# ChargeLevel.net
KiCad netlist of a schematic drawn in Altium Designer
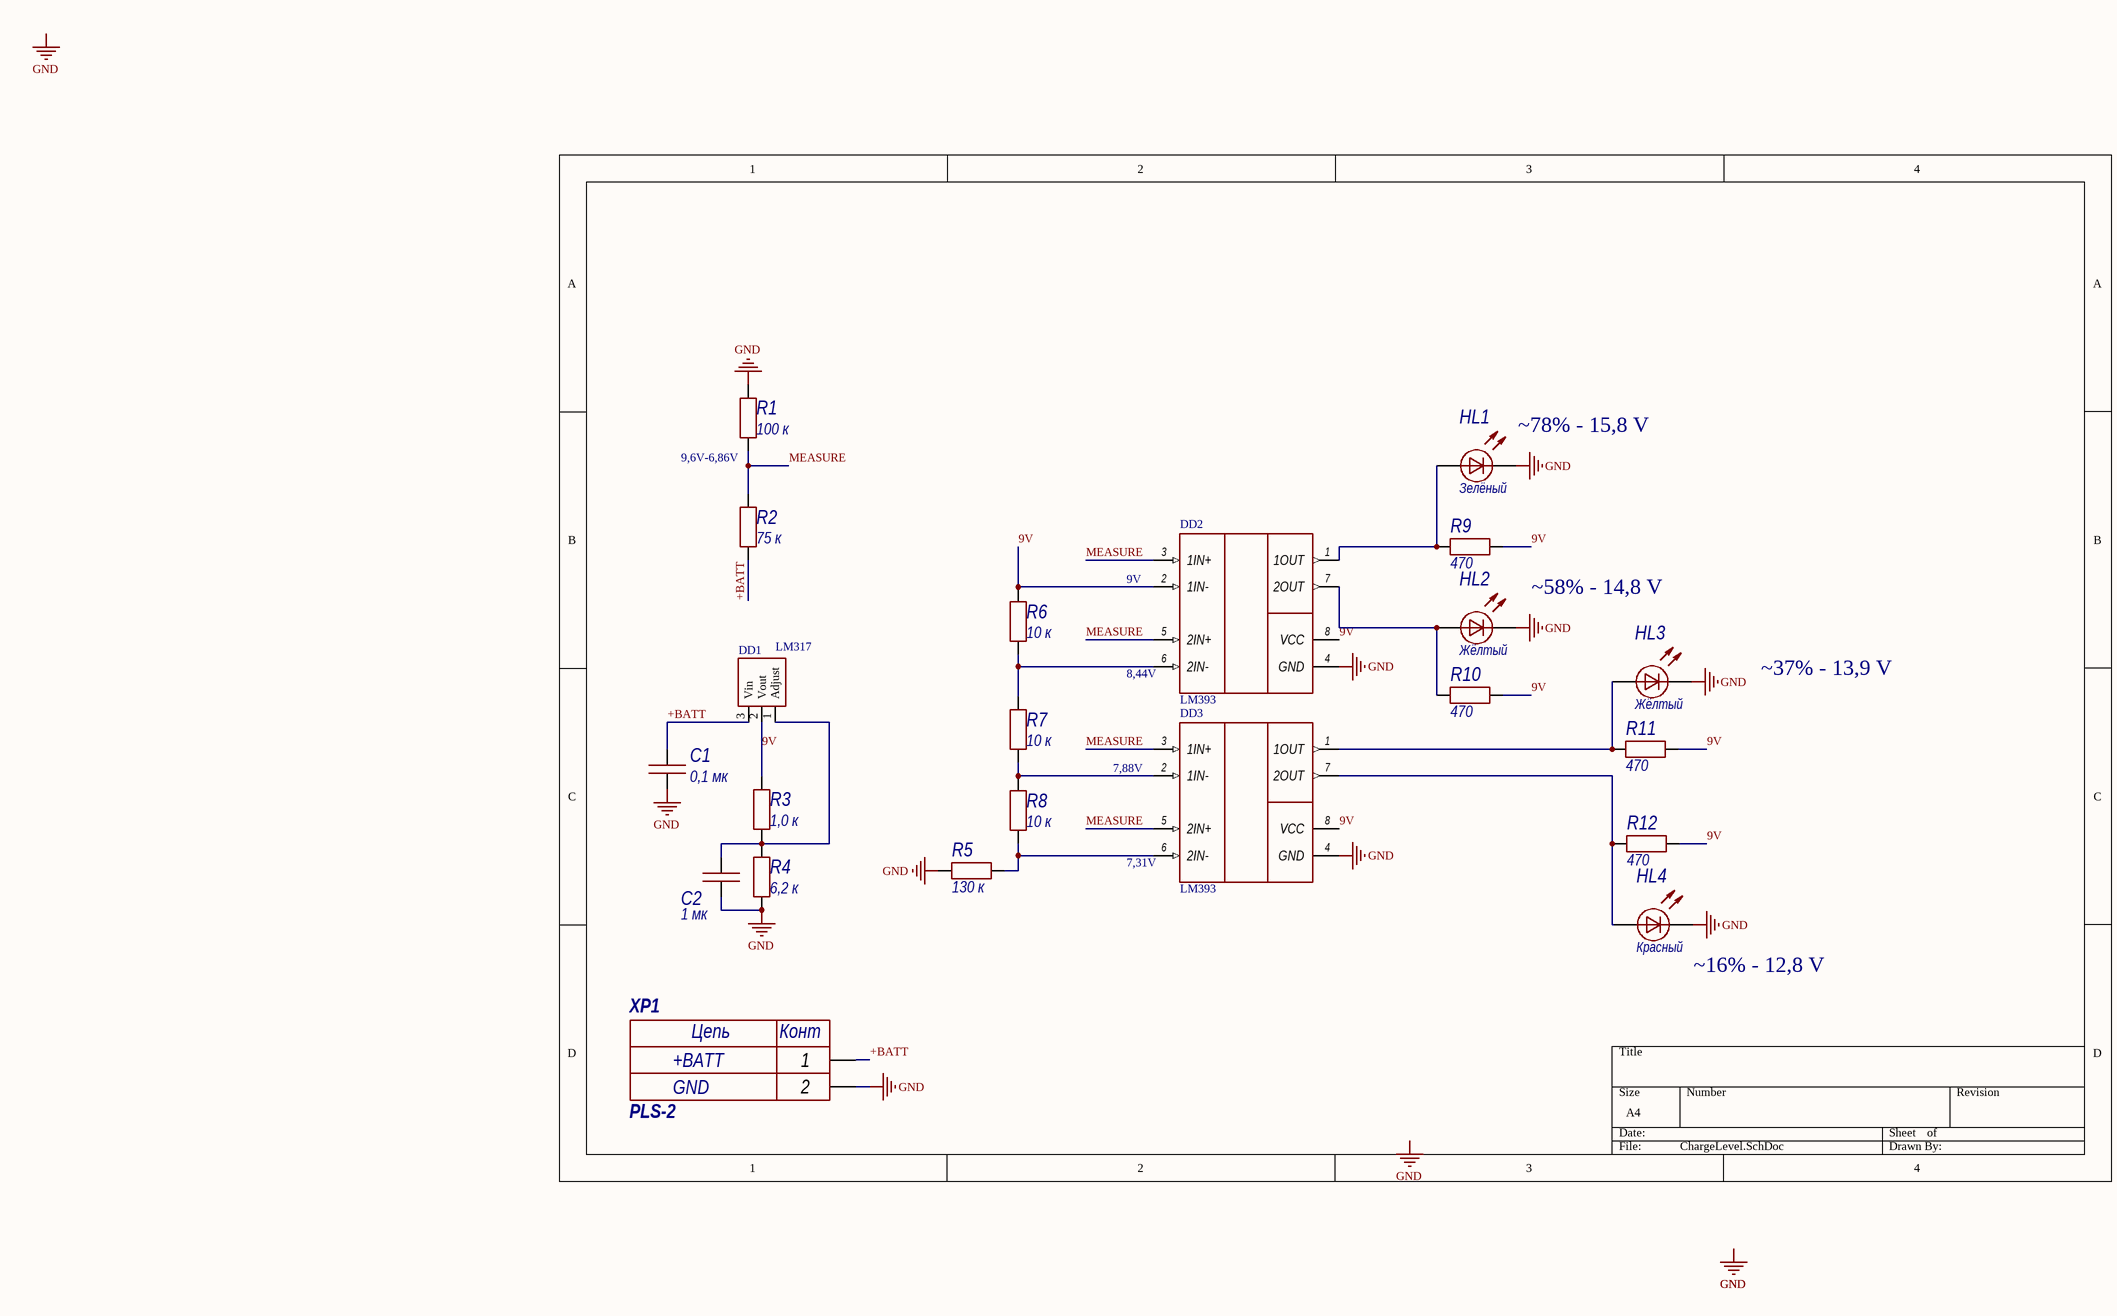
[diagram p0: ChargeLevel.SchDoc]

(export (version "E")
  (design (tool "Eeschema 10.0.6"))
  (components
    (comp (ref "C1")
      (value "0,1 мк")
      (footprint "0603C")
      (description "Конденсатор")
      (fields (field (name "PART NUMBER") "Capacitor"))
      (libsource (lib "Hydrolib") (part "Capacitor"))
    )
    (comp (ref "C2")
      (value "1 мк")
      (footprint "0603C")
      (description "Конденсатор")
      (fields (field (name "PART NUMBER") "Capacitor"))
      (libsource (lib "Hydrolib") (part "Capacitor"))
    )
    (comp (ref "DD1") (value "LM317") (footprint "TO-220") (libsource (lib "LM317") (part "LM317")))
    (comp (ref "DD2")
      (value "LM393")
      (footprint "SOIC-8")
      (description "Двойной маломощный компаратор напряжения")
      (fields
        (field (name "MF") "Texas Instruments")
        (field (name "MP") "LM393D")
        (field (name "АВТОР") "rreali")
      )
      (libsource (lib "Hydrolib") (part "LM393"))
    )
    (comp (ref "DD3")
      (value "LM393")
      (footprint "SOIC-8")
      (description "Двойной маломощный компаратор напряжения")
      (fields
        (field (name "MF") "Texas Instruments")
        (field (name "MP") "LM393D")
        (field (name "АВТОР") "rreali")
      )
      (libsource (lib "Hydrolib") (part "LM393"))
    )
    (comp (ref "HL1")
      (value "Зелёный")
      (footprint "0603D_green")
      (description "Светодиод 0603 Зелёный")
      (fields (field (name "PART NUMBER") "LED 0603 GREEN") (field (name "АВТОР") "rreali"))
      (libsource (lib "Hydrolib") (part "LED"))
    )
    (comp (ref "HL2")
      (value "Жёлтый")
      (footprint "0603D_yellow")
      (description "Светодиод 0603 Жёлтый")
      (fields (field (name "PART NUMBER") "LED 0603 YELLOW") (field (name "АВТОР") "rreali"))
      (libsource (lib "Hydrolib") (part "LED"))
    )
    (comp (ref "HL3")
      (value "Жёлтый")
      (footprint "0603D_yellow")
      (description "Светодиод 0603 Жёлтый")
      (fields (field (name "PART NUMBER") "LED 0603 YELLOW") (field (name "АВТОР") "rreali"))
      (libsource (lib "Hydrolib") (part "LED"))
    )
    (comp (ref "HL4")
      (value "Красный")
      (footprint "0603D_red")
      (description "Светодиод 0603 Красный")
      (fields (field (name "PART NUMBER") "LED 0603 RED") (field (name "АВТОР") "rreali"))
      (libsource (lib "Hydrolib") (part "LED"))
    )
    (comp (ref "R1")
      (value "100 к")
      (footprint "0603R")
      (description "Резистор номиналом 100 кОм 1%")
      (fields (field (name "PART NUMBER") "Resistor_100k_1_0603") (field (name "TOLERANCE") "1%"))
      (libsource (lib "") (part "Resistor_1"))
    )
    (comp (ref "R2")
      (value "75 к")
      (footprint "0603R")
      (description "Резистор номиналом 75 кОм 1%")
      (fields (field (name "PART NUMBER") "Resistor_75k_1_0603") (field (name "TOLERANCE") "1%"))
      (libsource (lib "") (part "Resistor_1"))
    )
    (comp (ref "R3")
      (value "1,0 к")
      (footprint "0603R")
      (description "Резистор номиналом 1,0 кОм 1%")
      (fields (field (name "PART NUMBER") "Resistor_1.0k_1_0603") (field (name "TOLERANCE") "1%"))
      (libsource (lib "") (part "Resistor_1"))
    )
    (comp (ref "R4")
      (value "6,2 к")
      (footprint "0603R")
      (description "Резистор номиналом 6,2 кОм 1%")
      (fields (field (name "PART NUMBER") "Resistor_6.2k_1_0603") (field (name "TOLERANCE") "1%"))
      (libsource (lib "") (part "Resistor_1"))
    )
    (comp (ref "R5")
      (value "130 к")
      (footprint "0603R")
      (description "Резистор номиналом 130 кОм 1%")
      (fields (field (name "PART NUMBER") "Resistor_130k_1_0603") (field (name "TOLERANCE") "1%"))
      (libsource (lib "Hydrolib") (part "Resistor"))
    )
    (comp (ref "R6")
      (value "10 к")
      (footprint "0603R")
      (description "Резистор номиналом 10 кОм 1%")
      (fields (field (name "PART NUMBER") "Resistor_10k_1_0603") (field (name "TOLERANCE") "1%"))
      (libsource (lib "") (part "Resistor_1"))
    )
    (comp (ref "R7")
      (value "10 к")
      (footprint "0603R")
      (description "Резистор номиналом 10 кОм 1%")
      (fields (field (name "PART NUMBER") "Resistor_10k_1_0603") (field (name "TOLERANCE") "1%"))
      (libsource (lib "") (part "Resistor_1"))
    )
    (comp (ref "R8")
      (value "10 к")
      (footprint "0603R")
      (description "Резистор номиналом 10 кОм 1%")
      (fields (field (name "PART NUMBER") "Resistor_10k_1_0603") (field (name "TOLERANCE") "1%"))
      (libsource (lib "") (part "Resistor_1"))
    )
    (comp (ref "R9")
      (value "470")
      (footprint "0603R")
      (description "Резистор номиналом 470 Ом 1%")
      (fields (field (name "PART NUMBER") "Resistor_470_1_0603") (field (name "TOLERANCE") "1%"))
      (libsource (lib "Hydrolib") (part "Resistor"))
    )
    (comp (ref "R10")
      (value "470")
      (footprint "0603R")
      (description "Резистор номиналом 470 Ом 1%")
      (fields (field (name "PART NUMBER") "Resistor_470_1_0603") (field (name "TOLERANCE") "1%"))
      (libsource (lib "Hydrolib") (part "Resistor"))
    )
    (comp (ref "R11")
      (value "470")
      (footprint "0603R")
      (description "Резистор номиналом 470 Ом 1%")
      (fields (field (name "PART NUMBER") "Resistor_470_1_0603") (field (name "TOLERANCE") "1%"))
      (libsource (lib "Hydrolib") (part "Resistor"))
    )
    (comp (ref "R12")
      (value "470")
      (footprint "0603R")
      (description "Резистор номиналом 470 Ом 1%")
      (fields (field (name "PART NUMBER") "Resistor_470_1_0603") (field (name "TOLERANCE") "1%"))
      (libsource (lib "Hydrolib") (part "Resistor"))
    )
    (comp (ref "XP1")
      (value "PLS-2")
      (footprint "PLS2")
      (description "Гребенка 2 пина")
      (fields (field (name "VALUE2") "GND") (field (name "VALUE1") "+BATT") (field (name "АВТОР") "rreali"))
      (libsource (lib "Hydrolib") (part "Conn_2pin"))
    )
  )
  (nets
    (net (code "1") (name "/+BATT") (class "Default")
      (node (ref "C1") (pin "1") (pinfunction "1_1") (pintype "passive"))
      (node (ref "DD1") (pin "3") (pinfunction "Vin_3") (pintype "passive"))
      (node (ref "R2") (pin "1") (pinfunction "1_1") (pintype "passive"))
      (node (ref "XP1") (pin "1") (pinfunction "1_1") (pintype "passive"))
    )
    (net (code "2") (name "/9V") (class "Default")
      (node (ref "DD1") (pin "2") (pinfunction "Vout_2") (pintype "passive"))
      (node (ref "DD2") (pin "2") (pinfunction "1IN-_2") (pintype "input"))
      (node (ref "DD2") (pin "8") (pinfunction "VCC_8") (pintype "power_in"))
      (node (ref "DD3") (pin "8") (pinfunction "VCC_8") (pintype "power_in"))
      (node (ref "R10") (pin "2") (pinfunction "2_2") (pintype "passive"))
      (node (ref "R11") (pin "2") (pinfunction "2_2") (pintype "passive"))
      (node (ref "R12") (pin "2") (pinfunction "2_2") (pintype "passive"))
      (node (ref "R3") (pin "2") (pinfunction "2_2") (pintype "passive"))
      (node (ref "R6") (pin "2") (pinfunction "2_2") (pintype "passive"))
      (node (ref "R9") (pin "2") (pinfunction "2_2") (pintype "passive"))
    )
    (net (code "3") (name "/MEASURE") (class "Default")
      (node (ref "DD2") (pin "3") (pinfunction "1IN+_3") (pintype "input"))
      (node (ref "DD2") (pin "5") (pinfunction "2IN+_5") (pintype "input"))
      (node (ref "DD3") (pin "3") (pinfunction "1IN+_3") (pintype "input"))
      (node (ref "DD3") (pin "5") (pinfunction "2IN+_5") (pintype "input"))
      (node (ref "R1") (pin "1") (pinfunction "1_1") (pintype "passive"))
      (node (ref "R2") (pin "2") (pinfunction "2_2") (pintype "passive"))
    )
    (net (code "4") (name "GND") (class "Default")
      (node (ref "C1") (pin "2") (pinfunction "2_2") (pintype "passive"))
      (node (ref "C2") (pin "2") (pinfunction "2_2") (pintype "passive"))
      (node (ref "DD2") (pin "4") (pinfunction "GND_4") (pintype "power_in"))
      (node (ref "DD3") (pin "4") (pinfunction "GND_4") (pintype "power_in"))
      (node (ref "HL1") (pin "2") (pinfunction "2_2") (pintype "passive"))
      (node (ref "HL2") (pin "2") (pinfunction "2_2") (pintype "passive"))
      (node (ref "HL3") (pin "2") (pinfunction "2_2") (pintype "passive"))
      (node (ref "HL4") (pin "2") (pinfunction "2_2") (pintype "passive"))
      (node (ref "R1") (pin "2") (pinfunction "2_2") (pintype "passive"))
      (node (ref "R4") (pin "1") (pinfunction "1_1") (pintype "passive"))
      (node (ref "R5") (pin "1") (pinfunction "1_1") (pintype "passive"))
      (node (ref "XP1") (pin "2") (pinfunction "2_2") (pintype "passive"))
    )
    (net (code "5") (name "Net-(DD1-Adjust)") (class "Default")
      (node (ref "C2") (pin "1") (pinfunction "1_1") (pintype "passive"))
      (node (ref "DD1") (pin "1") (pinfunction "Adjust_1") (pintype "passive"))
      (node (ref "R3") (pin "1") (pinfunction "1_1") (pintype "passive"))
      (node (ref "R4") (pin "2") (pinfunction "2_2") (pintype "passive"))
    )
    (net (code "6") (name "Net-(DD2-1OUT)") (class "Default")
      (node (ref "DD2") (pin "1") (pinfunction "1OUT_1") (pintype "output"))
      (node (ref "HL1") (pin "1") (pinfunction "1_1") (pintype "passive"))
      (node (ref "R9") (pin "1") (pinfunction "1_1") (pintype "passive"))
    )
    (net (code "7") (name "Net-(DD2-2IN-)") (class "Default")
      (node (ref "DD2") (pin "6") (pinfunction "2IN-_6") (pintype "input"))
      (node (ref "R6") (pin "1") (pinfunction "1_1") (pintype "passive"))
      (node (ref "R7") (pin "2") (pinfunction "2_2") (pintype "passive"))
    )
    (net (code "8") (name "Net-(DD2-2OUT)") (class "Default")
      (node (ref "DD2") (pin "7") (pinfunction "2OUT_7") (pintype "output"))
      (node (ref "HL2") (pin "1") (pinfunction "1_1") (pintype "passive"))
      (node (ref "R10") (pin "1") (pinfunction "1_1") (pintype "passive"))
    )
    (net (code "9") (name "Net-(DD3-1IN-)") (class "Default")
      (node (ref "DD3") (pin "2") (pinfunction "1IN-_2") (pintype "input"))
      (node (ref "R7") (pin "1") (pinfunction "1_1") (pintype "passive"))
      (node (ref "R8") (pin "2") (pinfunction "2_2") (pintype "passive"))
    )
    (net (code "10") (name "Net-(DD3-1OUT)") (class "Default")
      (node (ref "DD3") (pin "1") (pinfunction "1OUT_1") (pintype "output"))
      (node (ref "HL3") (pin "1") (pinfunction "1_1") (pintype "passive"))
      (node (ref "R11") (pin "1") (pinfunction "1_1") (pintype "passive"))
    )
    (net (code "11") (name "Net-(DD3-2IN-)") (class "Default")
      (node (ref "DD3") (pin "6") (pinfunction "2IN-_6") (pintype "input"))
      (node (ref "R5") (pin "2") (pinfunction "2_2") (pintype "passive"))
      (node (ref "R8") (pin "1") (pinfunction "1_1") (pintype "passive"))
    )
    (net (code "12") (name "Net-(DD3-2OUT)") (class "Default")
      (node (ref "DD3") (pin "7") (pinfunction "2OUT_7") (pintype "output"))
      (node (ref "HL4") (pin "1") (pinfunction "1_1") (pintype "passive"))
      (node (ref "R12") (pin "1") (pinfunction "1_1") (pintype "passive"))
    )
  )
)
